# ND_PCR.net
KiCad netlist of a schematic drawn in EAGLE
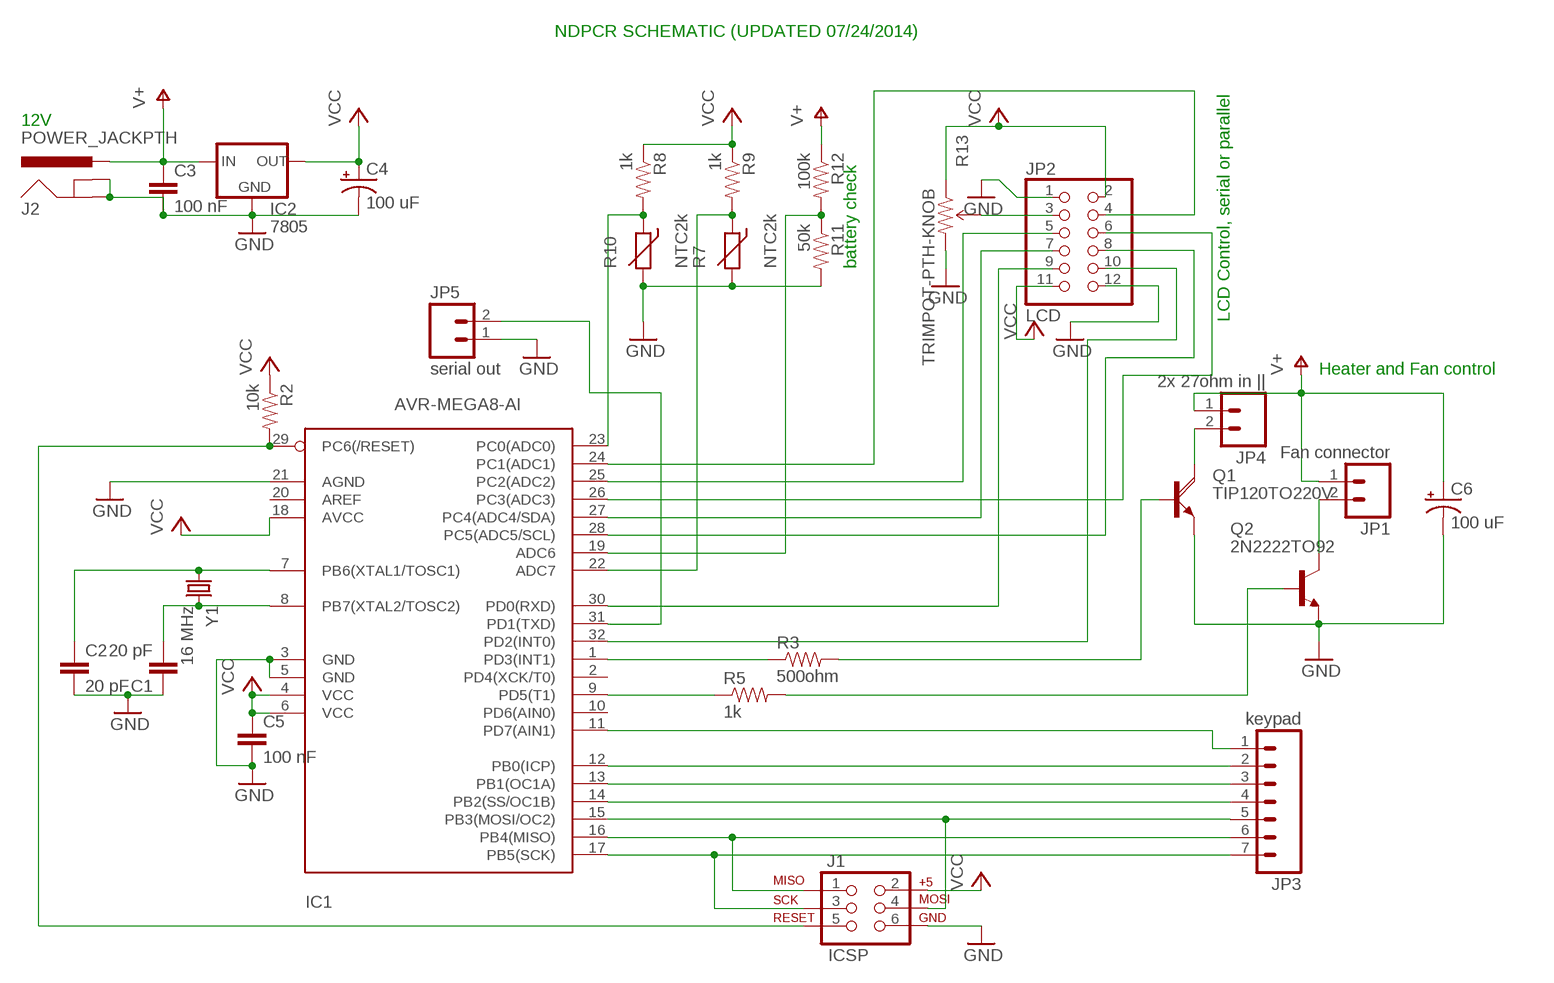
[diagram p0: schematic, sheet 1]

(export (version "E")
  (design (tool "Eeschema 10.0.6"))
  (components
    (comp (ref "C1")
      (value "20 pF")
      (footprint "eagle-import:CAP-PTH-SMALL")
      (libsource (lib "eagle-import") (part "CAPPTH"))
    )
    (comp (ref "C2")
      (value "20 pF")
      (footprint "eagle-import:CAP-PTH-SMALL")
      (libsource (lib "eagle-import") (part "CAPPTH"))
    )
    (comp (ref "C3")
      (value "100 nF")
      (footprint "eagle-import:CAP-PTH-SMALL")
      (libsource (lib "eagle-import") (part "CAPPTH"))
    )
    (comp (ref "C4")
      (value "100 uF")
      (footprint "eagle-import:CPOL-RADIAL-100UF-25V")
      (libsource (lib "eagle-import") (part "CAP_POLPTH1"))
    )
    (comp (ref "C5")
      (value "100 nF")
      (footprint "eagle-import:CAP-PTH-SMALL")
      (libsource (lib "eagle-import") (part "CAPPTH"))
    )
    (comp (ref "C6")
      (value "100 uF")
      (footprint "eagle-import:CPOL-RADIAL-100UF-25V")
      (libsource (lib "eagle-import") (part "CAP_POLPTH1"))
    )
    (comp (ref "IC1")
      (value "AVR-MEGA8-AI")
      (footprint "eagle-import:TQFP32-08")
      (libsource (lib "eagle-import") (part "AVR-MEGA8-AI"))
    )
    (comp (ref "IC2")
      (value "7805")
      (footprint "eagle-import:78XXS")
      (libsource (lib "eagle-import") (part "78XXS"))
    )
    (comp (ref "J1")
      (value "ICSP")
      (footprint "eagle-import:2X3")
      (libsource (lib "eagle-import") (part "AVR_SPI_PRG_6PTH"))
    )
    (comp (ref "J2")
      (value "POWER_JACKPTH")
      (footprint "eagle-import:POWER_JACK_PTH")
      (libsource (lib "eagle-import") (part "POWER_JACKPTH"))
    )
    (comp (ref "JP1")
      (value "Fan connector")
      (footprint "eagle-import:1X02_LOCK")
      (libsource (lib "eagle-import") (part "M02LOCK"))
    )
    (comp (ref "JP2")
      (value "LCD")
      (footprint "eagle-import:2X06")
      (libsource (lib "eagle-import") (part "PINHD-2X6"))
    )
    (comp (ref "JP3")
      (value "keypad")
      (footprint "eagle-import:1X07")
      (libsource (lib "eagle-import") (part "M07"))
    )
    (comp (ref "JP4")
      (value "2x 27ohm in ||")
      (footprint "eagle-import:1X02_LOCK")
      (libsource (lib "eagle-import") (part "M02LOCK"))
    )
    (comp (ref "JP5")
      (value "serial out")
      (footprint "eagle-import:1X02_LOCK")
      (libsource (lib "eagle-import") (part "M02LOCK"))
    )
    (comp (ref "Q1")
      (value "TIP120TO220V")
      (footprint "eagle-import:TO220AV")
      (libsource (lib "eagle-import") (part "TIP120TO220V"))
    )
    (comp (ref "Q2")
      (value "2N2222TO92")
      (footprint "eagle-import:TO92-EBC")
      (libsource (lib "eagle-import") (part "2N2222TO92"))
    )
    (comp (ref "R2")
      (value "10k")
      (footprint "eagle-import:AXIAL-0.5")
      (libsource (lib "eagle-import") (part "RESISTORPTH-1/2W"))
    )
    (comp (ref "R3")
      (value "500ohm")
      (footprint "eagle-import:AXIAL-0.5")
      (libsource (lib "eagle-import") (part "RESISTORPTH-1/2W"))
    )
    (comp (ref "R5")
      (value "1k")
      (footprint "eagle-import:AXIAL-0.5")
      (libsource (lib "eagle-import") (part "RESISTORPTH-1/2W"))
    )
    (comp (ref "R7")
      (value "NTC2k")
      (footprint "eagle-import:RS-2,5")
      (libsource (lib "eagle-import") (part "THERMISTOR-2,5"))
    )
    (comp (ref "R8")
      (value "1k")
      (footprint "eagle-import:AXIAL-0.5")
      (libsource (lib "eagle-import") (part "RESISTORPTH-1/2W"))
    )
    (comp (ref "R9")
      (value "1k")
      (footprint "eagle-import:AXIAL-0.5")
      (libsource (lib "eagle-import") (part "RESISTORPTH-1/2W"))
    )
    (comp (ref "R10")
      (value "NTC2k")
      (footprint "eagle-import:RS-2,5")
      (libsource (lib "eagle-import") (part "THERMISTOR-2,5"))
    )
    (comp (ref "R11")
      (value "50k")
      (footprint "eagle-import:AXIAL-0.5")
      (libsource (lib "eagle-import") (part "RESISTORPTH-1/2W"))
    )
    (comp (ref "R12")
      (value "100k")
      (footprint "eagle-import:AXIAL-0.5")
      (libsource (lib "eagle-import") (part "RESISTORPTH-1/2W"))
    )
    (comp (ref "R13")
      (value "TRIMPOT-PTH-KNOB")
      (footprint "eagle-import:3386U")
      (libsource (lib "eagle-import") (part "TRIMPOT-PTH-KNOB"))
    )
    (comp (ref "Y1")
      (value "16 MHz")
      (footprint "eagle-import:HC49US")
      (libsource (lib "eagle-import") (part "CRYSTALHC49US"))
    )
  )
  (nets
    (net (code "1") (name "GND") (class "Default")
      (node (ref "C1") (pin "1") (pinfunction "1_1") (pintype "passive"))
      (node (ref "C2") (pin "2") (pinfunction "2_2") (pintype "passive"))
      (node (ref "C3") (pin "2") (pinfunction "2_2") (pintype "passive"))
      (node (ref "C4") (pin "2") (pinfunction "-_2") (pintype "passive"))
      (node (ref "C5") (pin "2") (pinfunction "2_2") (pintype "passive"))
      (node (ref "C6") (pin "2") (pinfunction "-_2") (pintype "passive"))
      (node (ref "IC1") (pin "21") (pinfunction "AGND_21") (pintype "bidirectional"))
      (node (ref "IC1") (pin "3") (pinfunction "GND_3") (pintype "bidirectional"))
      (node (ref "IC1") (pin "5") (pinfunction "GND_5") (pintype "bidirectional"))
      (node (ref "IC2") (pin "GND") (pinfunction "GND_GND") (pintype "input"))
      (node (ref "J1") (pin "6") (pinfunction "6_6") (pintype "passive"))
      (node (ref "J2") (pin "GND") (pinfunction "GND_GND") (pintype "bidirectional"))
      (node (ref "J2") (pin "GNDBREAK") (pinfunction "GNDBREAK_GNDBREAK") (pintype "bidirectional"))
      (node (ref "JP2") (pin "1") (pinfunction "1_1") (pintype "passive"))
      (node (ref "JP2") (pin "12") (pinfunction "12_12") (pintype "passive"))
      (node (ref "JP5") (pin "1") (pinfunction "1_1") (pintype "passive"))
      (node (ref "Q1") (pin "E") (pinfunction "E_E") (pintype "passive"))
      (node (ref "Q2") (pin "C") (pinfunction "E_C") (pintype "passive"))
      (node (ref "R10") (pin "2") (pinfunction "2_2") (pintype "passive"))
      (node (ref "R11") (pin "P$2") (pinfunction "2_P$2") (pintype "passive"))
      (node (ref "R13") (pin "3") (pinfunction "CW_3") (pintype "passive"))
      (node (ref "R7") (pin "2") (pinfunction "2_2") (pintype "passive"))
    )
    (net (code "2") (name "Net-(IC1-ADC6)") (class "Default")
      (node (ref "IC1") (pin "19") (pinfunction "ADC6_19") (pintype "bidirectional"))
      (node (ref "R11") (pin "P$1") (pinfunction "1_P$1") (pintype "passive"))
      (node (ref "R12") (pin "P$2") (pinfunction "2_P$2") (pintype "passive"))
    )
    (net (code "3") (name "Net-(IC1-ADC7)") (class "Default")
      (node (ref "IC1") (pin "22") (pinfunction "ADC7_22") (pintype "bidirectional"))
      (node (ref "R7") (pin "1") (pinfunction "1_1") (pintype "passive"))
      (node (ref "R9") (pin "P$2") (pinfunction "2_P$2") (pintype "passive"))
    )
    (net (code "4") (name "Net-(IC1-PB0(ICP))") (class "Default")
      (node (ref "IC1") (pin "12") (pinfunction "PB0(ICP)_12") (pintype "bidirectional"))
      (node (ref "JP3") (pin "2") (pinfunction "2_2") (pintype "passive"))
    )
    (net (code "5") (name "Net-(IC1-PB1(OC1A))") (class "Default")
      (node (ref "IC1") (pin "13") (pinfunction "PB1(OC1A)_13") (pintype "bidirectional"))
      (node (ref "JP3") (pin "3") (pinfunction "3_3") (pintype "passive"))
    )
    (net (code "6") (name "Net-(IC1-PB2(SS{slash}OC1B))") (class "Default")
      (node (ref "IC1") (pin "14") (pinfunction "PB2(SS/OC1B)_14") (pintype "bidirectional"))
      (node (ref "JP3") (pin "4") (pinfunction "4_4") (pintype "passive"))
    )
    (net (code "7") (name "Net-(IC1-PB3(MOSI{slash}OC2))") (class "Default")
      (node (ref "IC1") (pin "15") (pinfunction "PB3(MOSI/OC2)_15") (pintype "bidirectional"))
      (node (ref "J1") (pin "4") (pinfunction "4_4") (pintype "passive"))
      (node (ref "JP3") (pin "5") (pinfunction "5_5") (pintype "passive"))
    )
    (net (code "8") (name "Net-(IC1-PB4(MISO))") (class "Default")
      (node (ref "IC1") (pin "16") (pinfunction "PB4(MISO)_16") (pintype "bidirectional"))
      (node (ref "J1") (pin "1") (pinfunction "1_1") (pintype "passive"))
      (node (ref "JP3") (pin "6") (pinfunction "6_6") (pintype "passive"))
    )
    (net (code "9") (name "Net-(IC1-PB5(SCK))") (class "Default")
      (node (ref "IC1") (pin "17") (pinfunction "PB5(SCK)_17") (pintype "bidirectional"))
      (node (ref "J1") (pin "3") (pinfunction "3_3") (pintype "passive"))
      (node (ref "JP3") (pin "7") (pinfunction "7_7") (pintype "passive"))
    )
    (net (code "10") (name "Net-(IC1-PB6(XTAL1{slash}TOSC1))") (class "Default")
      (node (ref "C2") (pin "1") (pinfunction "1_1") (pintype "passive"))
      (node (ref "IC1") (pin "7") (pinfunction "PB6(XTAL1/TOSC1)_7") (pintype "bidirectional"))
      (node (ref "Y1") (pin "1") (pinfunction "1_1") (pintype "passive"))
    )
    (net (code "11") (name "Net-(IC1-PB7(XTAL2{slash}TOSC2))") (class "Default")
      (node (ref "C1") (pin "2") (pinfunction "2_2") (pintype "passive"))
      (node (ref "IC1") (pin "8") (pinfunction "PB7(XTAL2/TOSC2)_8") (pintype "bidirectional"))
      (node (ref "Y1") (pin "2") (pinfunction "2_2") (pintype "passive"))
    )
    (net (code "12") (name "Net-(IC1-PC0(ADC0))") (class "Default")
      (node (ref "IC1") (pin "23") (pinfunction "PC0(ADC0)_23") (pintype "bidirectional"))
      (node (ref "R10") (pin "1") (pinfunction "1_1") (pintype "passive"))
      (node (ref "R8") (pin "P$2") (pinfunction "2_P$2") (pintype "passive"))
    )
    (net (code "13") (name "Net-(IC1-PC1(ADC1))") (class "Default")
      (node (ref "IC1") (pin "24") (pinfunction "PC1(ADC1)_24") (pintype "bidirectional"))
      (node (ref "JP2") (pin "4") (pinfunction "4_4") (pintype "passive"))
    )
    (net (code "14") (name "Net-(IC1-PC2(ADC2))") (class "Default")
      (node (ref "IC1") (pin "25") (pinfunction "PC2(ADC2)_25") (pintype "bidirectional"))
      (node (ref "JP2") (pin "5") (pinfunction "5_5") (pintype "passive"))
    )
    (net (code "15") (name "Net-(IC1-PC3(ADC3))") (class "Default")
      (node (ref "IC1") (pin "26") (pinfunction "PC3(ADC3)_26") (pintype "bidirectional"))
      (node (ref "JP2") (pin "6") (pinfunction "6_6") (pintype "passive"))
    )
    (net (code "16") (name "Net-(IC1-PC4(ADC4{slash}SDA))") (class "Default")
      (node (ref "IC1") (pin "27") (pinfunction "PC4(ADC4/SDA)_27") (pintype "bidirectional"))
      (node (ref "JP2") (pin "7") (pinfunction "7_7") (pintype "passive"))
    )
    (net (code "17") (name "Net-(IC1-PC5(ADC5{slash}SCL))") (class "Default")
      (node (ref "IC1") (pin "28") (pinfunction "PC5(ADC5/SCL)_28") (pintype "bidirectional"))
      (node (ref "JP2") (pin "8") (pinfunction "8_8") (pintype "passive"))
    )
    (net (code "18") (name "Net-(IC1-PC6({slash}RESET))") (class "Default")
      (node (ref "IC1") (pin "29") (pinfunction "PC6(/RESET)_29") (pintype "bidirectional"))
      (node (ref "J1") (pin "5") (pinfunction "5_5") (pintype "passive"))
      (node (ref "R2") (pin "P$2") (pinfunction "2_P$2") (pintype "passive"))
    )
    (net (code "19") (name "Net-(IC1-PD0(RXD))") (class "Default")
      (node (ref "IC1") (pin "30") (pinfunction "PD0(RXD)_30") (pintype "bidirectional"))
      (node (ref "JP2") (pin "9") (pinfunction "9_9") (pintype "passive"))
    )
    (net (code "20") (name "Net-(IC1-PD1(TXD))") (class "Default")
      (node (ref "IC1") (pin "31") (pinfunction "PD1(TXD)_31") (pintype "bidirectional"))
      (node (ref "JP5") (pin "2") (pinfunction "2_2") (pintype "passive"))
    )
    (net (code "21") (name "Net-(IC1-PD2(INT0))") (class "Default")
      (node (ref "IC1") (pin "32") (pinfunction "PD2(INT0)_32") (pintype "bidirectional"))
      (node (ref "JP2") (pin "10") (pinfunction "10_10") (pintype "passive"))
    )
    (net (code "22") (name "Net-(IC1-PD3(INT1))") (class "Default")
      (node (ref "IC1") (pin "1") (pinfunction "PD3(INT1)_1") (pintype "bidirectional"))
      (node (ref "R3") (pin "P$1") (pinfunction "1_P$1") (pintype "passive"))
    )
    (net (code "23") (name "Net-(IC1-PD5(T1))") (class "Default")
      (node (ref "IC1") (pin "9") (pinfunction "PD5(T1)_9") (pintype "bidirectional"))
      (node (ref "R5") (pin "P$1") (pinfunction "1_P$1") (pintype "passive"))
    )
    (net (code "24") (name "Net-(IC1-PD7(AIN1))") (class "Default")
      (node (ref "IC1") (pin "11") (pinfunction "PD7(AIN1)_11") (pintype "bidirectional"))
      (node (ref "JP3") (pin "1") (pinfunction "1_1") (pintype "passive"))
    )
    (net (code "25") (name "Net-(JP4-Pad2)") (class "Default")
      (node (ref "JP4") (pin "2") (pinfunction "2_2") (pintype "passive"))
      (node (ref "Q1") (pin "C") (pinfunction "C_C") (pintype "passive"))
    )
    (net (code "26") (name "Net-(Q2-C)") (class "Default")
      (node (ref "JP1") (pin "2") (pinfunction "2_2") (pintype "passive"))
      (node (ref "Q2") (pin "E") (pinfunction "C_E") (pintype "passive"))
    )
    (net (code "27") (name "Net-(R3-2)") (class "Default")
      (node (ref "Q1") (pin "B") (pinfunction "B_B") (pintype "passive"))
      (node (ref "R3") (pin "P$2") (pinfunction "2_P$2") (pintype "passive"))
    )
    (net (code "28") (name "Net-(R5-2)") (class "Default")
      (node (ref "Q2") (pin "B") (pinfunction "B_B") (pintype "passive"))
      (node (ref "R5") (pin "P$2") (pinfunction "2_P$2") (pintype "passive"))
    )
    (net (code "29") (name "Net-(R13-WIPER)") (class "Default")
      (node (ref "JP2") (pin "3") (pinfunction "3_3") (pintype "passive"))
      (node (ref "R13") (pin "2") (pinfunction "WIPER_2") (pintype "passive"))
    )
    (net (code "30") (name "V+") (class "Default")
      (node (ref "C3") (pin "1") (pinfunction "1_1") (pintype "passive"))
      (node (ref "C6") (pin "1") (pinfunction "+_1") (pintype "passive"))
      (node (ref "IC2") (pin "IN") (pinfunction "IN_IN") (pintype "input"))
      (node (ref "J2") (pin "PWR") (pinfunction "PWR_PWR") (pintype "bidirectional"))
      (node (ref "JP1") (pin "1") (pinfunction "1_1") (pintype "passive"))
      (node (ref "JP4") (pin "1") (pinfunction "1_1") (pintype "passive"))
      (node (ref "R12") (pin "P$1") (pinfunction "1_P$1") (pintype "passive"))
    )
    (net (code "31") (name "VCC") (class "Default")
      (node (ref "C4") (pin "1") (pinfunction "+_1") (pintype "passive"))
      (node (ref "C5") (pin "1") (pinfunction "1_1") (pintype "passive"))
      (node (ref "IC1") (pin "18") (pinfunction "AVCC_18") (pintype "bidirectional"))
      (node (ref "IC1") (pin "4") (pinfunction "VCC_4") (pintype "bidirectional"))
      (node (ref "IC1") (pin "6") (pinfunction "VCC_6") (pintype "bidirectional"))
      (node (ref "IC2") (pin "OUT") (pinfunction "OUT_OUT") (pintype "passive"))
      (node (ref "J1") (pin "2") (pinfunction "2_2") (pintype "passive"))
      (node (ref "JP2") (pin "11") (pinfunction "11_11") (pintype "passive"))
      (node (ref "JP2") (pin "2") (pinfunction "2_2") (pintype "passive"))
      (node (ref "R13") (pin "1") (pinfunction "CCW_1") (pintype "passive"))
      (node (ref "R2") (pin "P$1") (pinfunction "1_P$1") (pintype "passive"))
      (node (ref "R8") (pin "P$1") (pinfunction "1_P$1") (pintype "passive"))
      (node (ref "R9") (pin "P$1") (pinfunction "1_P$1") (pintype "passive"))
    )
    (net (code "32") (name "unconnected-(IC1-AREF-Pad20)") (class "Default")
      (node (ref "IC1") (pin "20") (pinfunction "AREF_20") (pintype "bidirectional"))
    )
    (net (code "33") (name "unconnected-(IC1-PD4(XCK{slash}T0)-Pad2)") (class "Default")
      (node (ref "IC1") (pin "2") (pinfunction "PD4(XCK/T0)_2") (pintype "bidirectional"))
    )
    (net (code "34") (name "unconnected-(IC1-PD6(AIN0)-Pad10)") (class "Default")
      (node (ref "IC1") (pin "10") (pinfunction "PD6(AIN0)_10") (pintype "bidirectional"))
    )
  )
)
